# 05_PWMdriver.net
KiCad netlist of a schematic drawn in Altium Designer
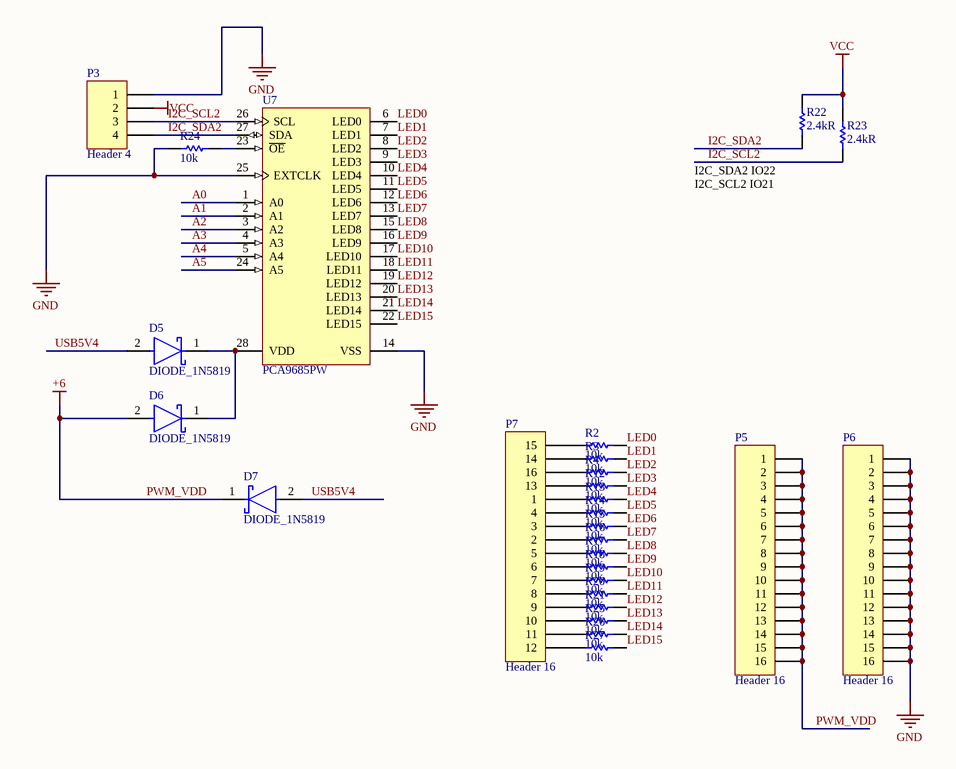
[diagram p0: 05_PWMdriver.SchDoc]

(export (version "E")
  (design (tool "Eeschema 10.0.6"))
  (components
    (comp (ref "D5")
      (value "DIODE_1N5819")
      (footprint "FP-SOD123-MFG")
      (description "DIODE SCHOTTKY 40V 1A SOD123")
      (fields
        (field (name "OCTOPART") "https://octopart.com/1n5819hw-7-f-diodes+inc.-323197")
        (field (name "MANUFACTURER") "Diodes Inc")
      )
      (libsource (lib "Altium Content Vault") (part "1d6ec82d83fb6aee721767c19dac4b9"))
    )
    (comp (ref "D6")
      (value "DIODE_1N5819")
      (footprint "FP-SOD123-MFG")
      (description "DIODE SCHOTTKY 40V 1A SOD123")
      (fields
        (field (name "OCTOPART") "https://octopart.com/1n5819hw-7-f-diodes+inc.-323197")
        (field (name "MANUFACTURER") "Diodes Inc")
      )
      (libsource (lib "Altium Content Vault") (part "1d6ec82d83fb6aee721767c19dac4b9"))
    )
    (comp (ref "D7")
      (value "DIODE_1N5819")
      (footprint "FP-SOD123-MFG")
      (description "DIODE SCHOTTKY 40V 1A SOD123")
      (fields
        (field (name "OCTOPART") "https://octopart.com/1n5819hw-7-f-diodes+inc.-323197")
        (field (name "MANUFACTURER") "Diodes Inc")
      )
      (libsource (lib "Altium Content Vault") (part "1d6ec82d83fb6aee721767c19dac4b9"))
    )
    (comp (ref "P3")
      (value "Header 4")
      (footprint "HDR1X4")
      (description "Header, 4-Pin")
      (fields (field (name "PUBLISHER") "Altium Limited"))
      (libsource (lib "Miscellaneous Connectors") (part "Header 4"))
    )
    (comp (ref "P5")
      (value "Header 16")
      (footprint "HDR1X16")
      (description "Header, 16-Pin")
      (fields (field (name "PUBLISHER") "Altium Limited"))
      (libsource (lib "Miscellaneous Connectors") (part "Header 16"))
    )
    (comp (ref "P6")
      (value "Header 16")
      (footprint "HDR1X16")
      (description "Header, 16-Pin")
      (fields (field (name "PUBLISHER") "Altium Limited"))
      (libsource (lib "Miscellaneous Connectors") (part "Header 16"))
    )
    (comp (ref "P7")
      (value "Header 16")
      (footprint "HDR1X16")
      (description "Header, 16-Pin")
      (fields (field (name "PUBLISHER") "Altium Limited"))
      (libsource (lib "") (part "Header 16_1"))
    )
    (comp (ref "R2")
      (value "10k")
      (footprint "RESC1609X55X30LL15T15")
      (description "Chip Resistor, 10 KOhm, +/- 1%, 0.1 W, -55 to 155 degC, 0603 (1608 Metric), RoHS, Tape and Reel")
      (fields (field (name "TOLERANCE") "1%") (field (name "MANUFACTURER") "Panasonic"))
      (libsource (lib "Altium Content Vault") (part "RES-2"))
    )
    (comp (ref "R3")
      (value "10k")
      (footprint "RESC1609X55X30LL15T15")
      (description "Chip Resistor, 10 KOhm, +/- 1%, 0.1 W, -55 to 155 degC, 0603 (1608 Metric), RoHS, Tape and Reel")
      (fields (field (name "TOLERANCE") "1%") (field (name "MANUFACTURER") "Panasonic"))
      (libsource (lib "Altium Content Vault") (part "RES-2"))
    )
    (comp (ref "R4")
      (value "10k")
      (footprint "RESC1609X55X30LL15T15")
      (description "Chip Resistor, 10 KOhm, +/- 1%, 0.1 W, -55 to 155 degC, 0603 (1608 Metric), RoHS, Tape and Reel")
      (fields (field (name "TOLERANCE") "1%") (field (name "MANUFACTURER") "Panasonic"))
      (libsource (lib "Altium Content Vault") (part "RES-2"))
    )
    (comp (ref "R12")
      (value "10k")
      (footprint "RESC1609X55X30LL15T15")
      (description "Chip Resistor, 10 KOhm, +/- 1%, 0.1 W, -55 to 155 degC, 0603 (1608 Metric), RoHS, Tape and Reel")
      (fields (field (name "TOLERANCE") "1%") (field (name "MANUFACTURER") "Panasonic"))
      (libsource (lib "Altium Content Vault") (part "RES-2"))
    )
    (comp (ref "R13")
      (value "10k")
      (footprint "RESC1609X55X30LL15T15")
      (description "Chip Resistor, 10 KOhm, +/- 1%, 0.1 W, -55 to 155 degC, 0603 (1608 Metric), RoHS, Tape and Reel")
      (fields (field (name "TOLERANCE") "1%") (field (name "MANUFACTURER") "Panasonic"))
      (libsource (lib "Altium Content Vault") (part "RES-2"))
    )
    (comp (ref "R14")
      (value "10k")
      (footprint "RESC1609X55X30LL15T15")
      (description "Chip Resistor, 10 KOhm, +/- 1%, 0.1 W, -55 to 155 degC, 0603 (1608 Metric), RoHS, Tape and Reel")
      (fields (field (name "TOLERANCE") "1%") (field (name "MANUFACTURER") "Panasonic"))
      (libsource (lib "Altium Content Vault") (part "RES-2"))
    )
    (comp (ref "R15")
      (value "10k")
      (footprint "RESC1609X55X30LL15T15")
      (description "Chip Resistor, 10 KOhm, +/- 1%, 0.1 W, -55 to 155 degC, 0603 (1608 Metric), RoHS, Tape and Reel")
      (fields (field (name "TOLERANCE") "1%") (field (name "MANUFACTURER") "Panasonic"))
      (libsource (lib "Altium Content Vault") (part "RES-2"))
    )
    (comp (ref "R16")
      (value "10k")
      (footprint "RESC1609X55X30LL15T15")
      (description "Chip Resistor, 10 KOhm, +/- 1%, 0.1 W, -55 to 155 degC, 0603 (1608 Metric), RoHS, Tape and Reel")
      (fields (field (name "TOLERANCE") "1%") (field (name "MANUFACTURER") "Panasonic"))
      (libsource (lib "Altium Content Vault") (part "RES-2"))
    )
    (comp (ref "R17")
      (value "10k")
      (footprint "RESC1609X55X30LL15T15")
      (description "Chip Resistor, 10 KOhm, +/- 1%, 0.1 W, -55 to 155 degC, 0603 (1608 Metric), RoHS, Tape and Reel")
      (fields (field (name "TOLERANCE") "1%") (field (name "MANUFACTURER") "Panasonic"))
      (libsource (lib "Altium Content Vault") (part "RES-2"))
    )
    (comp (ref "R18")
      (value "10k")
      (footprint "RESC1609X55X30LL15T15")
      (description "Chip Resistor, 10 KOhm, +/- 1%, 0.1 W, -55 to 155 degC, 0603 (1608 Metric), RoHS, Tape and Reel")
      (fields (field (name "TOLERANCE") "1%") (field (name "MANUFACTURER") "Panasonic"))
      (libsource (lib "Altium Content Vault") (part "RES-2"))
    )
    (comp (ref "R19")
      (value "10k")
      (footprint "RESC1609X55X30LL15T15")
      (description "Chip Resistor, 10 KOhm, +/- 1%, 0.1 W, -55 to 155 degC, 0603 (1608 Metric), RoHS, Tape and Reel")
      (fields (field (name "TOLERANCE") "1%") (field (name "MANUFACTURER") "Panasonic"))
      (libsource (lib "Altium Content Vault") (part "RES-2"))
    )
    (comp (ref "R20")
      (value "10k")
      (footprint "RESC1609X55X30LL15T15")
      (description "Chip Resistor, 10 KOhm, +/- 1%, 0.1 W, -55 to 155 degC, 0603 (1608 Metric), RoHS, Tape and Reel")
      (fields (field (name "TOLERANCE") "1%") (field (name "MANUFACTURER") "Panasonic"))
      (libsource (lib "Altium Content Vault") (part "RES-2"))
    )
    (comp (ref "R21")
      (value "10k")
      (footprint "RESC1609X55X30LL15T15")
      (description "Chip Resistor, 10 KOhm, +/- 1%, 0.1 W, -55 to 155 degC, 0603 (1608 Metric), RoHS, Tape and Reel")
      (fields (field (name "TOLERANCE") "1%") (field (name "MANUFACTURER") "Panasonic"))
      (libsource (lib "Altium Content Vault") (part "RES-2"))
    )
    (comp (ref "R22")
      (value "2.4kR")
      (footprint "RESC1608X50X30ML20T20")
      (fields
        (field (name "PART NUMBER") "RR0816P-242-D")
        (field (name "MANUFACTURER") "Susumu")
        (field (name "Comment") "R0603_2.4K")
      )
      (libsource (lib "Altium Content Vault") (part "RES"))
    )
    (comp (ref "R23")
      (value "2.4kR")
      (footprint "RESC1608X50X30ML20T20")
      (fields
        (field (name "PART NUMBER") "RR0816P-242-D")
        (field (name "MANUFACTURER") "Susumu")
        (field (name "Comment") "R0603_2.4K")
      )
      (libsource (lib "Altium Content Vault") (part "RES"))
    )
    (comp (ref "R24")
      (value "10k")
      (footprint "RESC1609X55X30LL15T15")
      (description "Chip Resistor, 10 KOhm, +/- 1%, 0.1 W, -55 to 155 degC, 0603 (1608 Metric), RoHS, Tape and Reel")
      (fields (field (name "TOLERANCE") "1%") (field (name "MANUFACTURER") "Panasonic"))
      (libsource (lib "Altium Content Vault") (part "RES-2"))
    )
    (comp (ref "R25")
      (value "10k")
      (footprint "RESC1609X55X30LL15T15")
      (description "Chip Resistor, 10 KOhm, +/- 1%, 0.1 W, -55 to 155 degC, 0603 (1608 Metric), RoHS, Tape and Reel")
      (fields (field (name "TOLERANCE") "1%") (field (name "MANUFACTURER") "Panasonic"))
      (libsource (lib "Altium Content Vault") (part "RES-2"))
    )
    (comp (ref "R26")
      (value "10k")
      (footprint "RESC1609X55X30LL15T15")
      (description "Chip Resistor, 10 KOhm, +/- 1%, 0.1 W, -55 to 155 degC, 0603 (1608 Metric), RoHS, Tape and Reel")
      (fields (field (name "TOLERANCE") "1%") (field (name "MANUFACTURER") "Panasonic"))
      (libsource (lib "Altium Content Vault") (part "RES-2"))
    )
    (comp (ref "R27")
      (value "10k")
      (footprint "RESC1609X55X30LL15T15")
      (description "Chip Resistor, 10 KOhm, +/- 1%, 0.1 W, -55 to 155 degC, 0603 (1608 Metric), RoHS, Tape and Reel")
      (fields (field (name "TOLERANCE") "1%") (field (name "MANUFACTURER") "Panasonic"))
      (libsource (lib "Altium Content Vault") (part "RES-2"))
    )
    (comp (ref "U7")
      (value "PCA9685PW")
      (footprint "SOT361-1_V")
      (fields (field (name "PARTNUMBER") "PCA9685"))
      (libsource (lib "Altium Content Vault") (part "NXP-PCA9685-SOT361-1"))
    )
  )
  (nets
    (net (code "1") (name "+6") (class "Default")
      (node (ref "D6") (pin "2") (pinfunction "A_2") (pintype "passive"))
      (node (ref "D7") (pin "1") (pinfunction "C_1") (pintype "passive"))
      (node (ref "P5") (pin "1") (pinfunction "1_1") (pintype "passive"))
      (node (ref "P5") (pin "10") (pinfunction "10_10") (pintype "passive"))
      (node (ref "P5") (pin "11") (pinfunction "11_11") (pintype "passive"))
      (node (ref "P5") (pin "12") (pinfunction "12_12") (pintype "passive"))
      (node (ref "P5") (pin "13") (pinfunction "13_13") (pintype "passive"))
      (node (ref "P5") (pin "14") (pinfunction "14_14") (pintype "passive"))
      (node (ref "P5") (pin "15") (pinfunction "15_15") (pintype "passive"))
      (node (ref "P5") (pin "16") (pinfunction "16_16") (pintype "passive"))
      (node (ref "P5") (pin "2") (pinfunction "2_2") (pintype "passive"))
      (node (ref "P5") (pin "3") (pinfunction "3_3") (pintype "passive"))
      (node (ref "P5") (pin "4") (pinfunction "4_4") (pintype "passive"))
      (node (ref "P5") (pin "5") (pinfunction "5_5") (pintype "passive"))
      (node (ref "P5") (pin "6") (pinfunction "6_6") (pintype "passive"))
      (node (ref "P5") (pin "7") (pinfunction "7_7") (pintype "passive"))
      (node (ref "P5") (pin "8") (pinfunction "8_8") (pintype "passive"))
      (node (ref "P5") (pin "9") (pinfunction "9_9") (pintype "passive"))
    )
    (net (code "2") (name "/A0") (class "Default")
      (node (ref "U7") (pin "1") (pinfunction "A0_1") (pintype "input"))
    )
    (net (code "3") (name "/A1") (class "Default")
      (node (ref "U7") (pin "2") (pinfunction "A1_2") (pintype "input"))
    )
    (net (code "4") (name "/A2") (class "Default")
      (node (ref "U7") (pin "3") (pinfunction "A2_3") (pintype "input"))
    )
    (net (code "5") (name "/A3") (class "Default")
      (node (ref "U7") (pin "4") (pinfunction "A3_4") (pintype "input"))
    )
    (net (code "6") (name "/A4") (class "Default")
      (node (ref "U7") (pin "5") (pinfunction "A4_5") (pintype "input"))
    )
    (net (code "7") (name "/A5") (class "Default")
      (node (ref "U7") (pin "24") (pinfunction "A5_24") (pintype "input"))
    )
    (net (code "8") (name "/I2C_SCL2") (class "Default")
      (node (ref "P3") (pin "3") (pinfunction "3_3") (pintype "passive"))
      (node (ref "R23") (pin "1") (pinfunction "1_1") (pintype "passive"))
      (node (ref "U7") (pin "26") (pinfunction "SCL_26") (pintype "input"))
    )
    (net (code "9") (name "/I2C_SDA2") (class "Default")
      (node (ref "P3") (pin "4") (pinfunction "4_4") (pintype "passive"))
      (node (ref "R22") (pin "1") (pinfunction "1_1") (pintype "passive"))
      (node (ref "U7") (pin "27") (pinfunction "SDA_27") (pintype "bidirectional"))
    )
    (net (code "10") (name "/LED0") (class "Default")
      (node (ref "R2") (pin "1") (pinfunction "1_1") (pintype "passive"))
      (node (ref "U7") (pin "6") (pinfunction "LED0_6") (pintype "tri_state"))
    )
    (net (code "11") (name "/LED1") (class "Default")
      (node (ref "R3") (pin "1") (pinfunction "1_1") (pintype "passive"))
      (node (ref "U7") (pin "7") (pinfunction "LED1_7") (pintype "tri_state"))
    )
    (net (code "12") (name "/LED2") (class "Default")
      (node (ref "R4") (pin "1") (pinfunction "1_1") (pintype "passive"))
      (node (ref "U7") (pin "8") (pinfunction "LED2_8") (pintype "tri_state"))
    )
    (net (code "13") (name "/LED3") (class "Default")
      (node (ref "R12") (pin "1") (pinfunction "1_1") (pintype "passive"))
      (node (ref "U7") (pin "9") (pinfunction "LED3_9") (pintype "tri_state"))
    )
    (net (code "14") (name "/LED4") (class "Default")
      (node (ref "R13") (pin "1") (pinfunction "1_1") (pintype "passive"))
      (node (ref "U7") (pin "10") (pinfunction "LED4_10") (pintype "tri_state"))
    )
    (net (code "15") (name "/LED5") (class "Default")
      (node (ref "R14") (pin "1") (pinfunction "1_1") (pintype "passive"))
      (node (ref "U7") (pin "11") (pinfunction "LED5_11") (pintype "tri_state"))
    )
    (net (code "16") (name "/LED6") (class "Default")
      (node (ref "R15") (pin "1") (pinfunction "1_1") (pintype "passive"))
      (node (ref "U7") (pin "12") (pinfunction "LED6_12") (pintype "tri_state"))
    )
    (net (code "17") (name "/LED7") (class "Default")
      (node (ref "R16") (pin "1") (pinfunction "1_1") (pintype "passive"))
      (node (ref "U7") (pin "13") (pinfunction "LED7_13") (pintype "tri_state"))
    )
    (net (code "18") (name "/LED8") (class "Default")
      (node (ref "R17") (pin "1") (pinfunction "1_1") (pintype "passive"))
      (node (ref "U7") (pin "15") (pinfunction "LED8_15") (pintype "tri_state"))
    )
    (net (code "19") (name "/LED9") (class "Default")
      (node (ref "R18") (pin "1") (pinfunction "1_1") (pintype "passive"))
      (node (ref "U7") (pin "16") (pinfunction "LED9_16") (pintype "tri_state"))
    )
    (net (code "20") (name "/LED10") (class "Default")
      (node (ref "R19") (pin "1") (pinfunction "1_1") (pintype "passive"))
      (node (ref "U7") (pin "17") (pinfunction "LED10_17") (pintype "tri_state"))
    )
    (net (code "21") (name "/LED11") (class "Default")
      (node (ref "R20") (pin "1") (pinfunction "1_1") (pintype "passive"))
      (node (ref "U7") (pin "18") (pinfunction "LED11_18") (pintype "tri_state"))
    )
    (net (code "22") (name "/LED12") (class "Default")
      (node (ref "R21") (pin "1") (pinfunction "1_1") (pintype "passive"))
      (node (ref "U7") (pin "19") (pinfunction "LED12_19") (pintype "tri_state"))
    )
    (net (code "23") (name "/LED13") (class "Default")
      (node (ref "R25") (pin "1") (pinfunction "1_1") (pintype "passive"))
      (node (ref "U7") (pin "20") (pinfunction "LED13_20") (pintype "tri_state"))
    )
    (net (code "24") (name "/LED14") (class "Default")
      (node (ref "R26") (pin "1") (pinfunction "1_1") (pintype "passive"))
      (node (ref "U7") (pin "21") (pinfunction "LED14_21") (pintype "tri_state"))
    )
    (net (code "25") (name "/LED15") (class "Default")
      (node (ref "R27") (pin "1") (pinfunction "1_1") (pintype "passive"))
      (node (ref "U7") (pin "22") (pinfunction "LED15_22") (pintype "tri_state"))
    )
    (net (code "26") (name "/USB5V4") (class "Default")
      (node (ref "D5") (pin "2") (pinfunction "A_2") (pintype "passive"))
      (node (ref "D7") (pin "2") (pinfunction "A_2") (pintype "passive"))
    )
    (net (code "27") (name "GND") (class "Default")
      (node (ref "P3") (pin "1") (pinfunction "1_1") (pintype "passive"))
      (node (ref "P6") (pin "1") (pinfunction "1_1") (pintype "passive"))
      (node (ref "P6") (pin "10") (pinfunction "10_10") (pintype "passive"))
      (node (ref "P6") (pin "11") (pinfunction "11_11") (pintype "passive"))
      (node (ref "P6") (pin "12") (pinfunction "12_12") (pintype "passive"))
      (node (ref "P6") (pin "13") (pinfunction "13_13") (pintype "passive"))
      (node (ref "P6") (pin "14") (pinfunction "14_14") (pintype "passive"))
      (node (ref "P6") (pin "15") (pinfunction "15_15") (pintype "passive"))
      (node (ref "P6") (pin "16") (pinfunction "16_16") (pintype "passive"))
      (node (ref "P6") (pin "2") (pinfunction "2_2") (pintype "passive"))
      (node (ref "P6") (pin "3") (pinfunction "3_3") (pintype "passive"))
      (node (ref "P6") (pin "4") (pinfunction "4_4") (pintype "passive"))
      (node (ref "P6") (pin "5") (pinfunction "5_5") (pintype "passive"))
      (node (ref "P6") (pin "6") (pinfunction "6_6") (pintype "passive"))
      (node (ref "P6") (pin "7") (pinfunction "7_7") (pintype "passive"))
      (node (ref "P6") (pin "8") (pinfunction "8_8") (pintype "passive"))
      (node (ref "P6") (pin "9") (pinfunction "9_9") (pintype "passive"))
      (node (ref "R24") (pin "2") (pinfunction "2_2") (pintype "passive"))
      (node (ref "U7") (pin "14") (pinfunction "VSS_14") (pintype "power_in"))
      (node (ref "U7") (pin "25") (pinfunction "EXTCLK_25") (pintype "input"))
    )
    (net (code "28") (name "Net-(D5-C)") (class "Default")
      (node (ref "D5") (pin "1") (pinfunction "C_1") (pintype "passive"))
      (node (ref "D6") (pin "1") (pinfunction "C_1") (pintype "passive"))
      (node (ref "U7") (pin "28") (pinfunction "VDD_28") (pintype "power_in"))
    )
    (net (code "29") (name "Net-(P7-Pad1)") (class "Default")
      (node (ref "P7") (pin "1") (pinfunction "1_1") (pintype "passive"))
      (node (ref "R13") (pin "2") (pinfunction "2_2") (pintype "passive"))
    )
    (net (code "30") (name "Net-(P7-Pad2)") (class "Default")
      (node (ref "P7") (pin "2") (pinfunction "2_2") (pintype "passive"))
      (node (ref "R16") (pin "2") (pinfunction "2_2") (pintype "passive"))
    )
    (net (code "31") (name "Net-(P7-Pad3)") (class "Default")
      (node (ref "P7") (pin "3") (pinfunction "3_3") (pintype "passive"))
      (node (ref "R15") (pin "2") (pinfunction "2_2") (pintype "passive"))
    )
    (net (code "32") (name "Net-(P7-Pad4)") (class "Default")
      (node (ref "P7") (pin "4") (pinfunction "4_4") (pintype "passive"))
      (node (ref "R14") (pin "2") (pinfunction "2_2") (pintype "passive"))
    )
    (net (code "33") (name "Net-(P7-Pad5)") (class "Default")
      (node (ref "P7") (pin "5") (pinfunction "5_5") (pintype "passive"))
      (node (ref "R17") (pin "2") (pinfunction "2_2") (pintype "passive"))
    )
    (net (code "34") (name "Net-(P7-Pad6)") (class "Default")
      (node (ref "P7") (pin "6") (pinfunction "6_6") (pintype "passive"))
      (node (ref "R18") (pin "2") (pinfunction "2_2") (pintype "passive"))
    )
    (net (code "35") (name "Net-(P7-Pad7)") (class "Default")
      (node (ref "P7") (pin "7") (pinfunction "7_7") (pintype "passive"))
      (node (ref "R19") (pin "2") (pinfunction "2_2") (pintype "passive"))
    )
    (net (code "36") (name "Net-(P7-Pad8)") (class "Default")
      (node (ref "P7") (pin "8") (pinfunction "8_8") (pintype "passive"))
      (node (ref "R20") (pin "2") (pinfunction "2_2") (pintype "passive"))
    )
    (net (code "37") (name "Net-(P7-Pad9)") (class "Default")
      (node (ref "P7") (pin "9") (pinfunction "9_9") (pintype "passive"))
      (node (ref "R21") (pin "2") (pinfunction "2_2") (pintype "passive"))
    )
    (net (code "38") (name "Net-(P7-Pad10)") (class "Default")
      (node (ref "P7") (pin "10") (pinfunction "10_10") (pintype "passive"))
      (node (ref "R25") (pin "2") (pinfunction "2_2") (pintype "passive"))
    )
    (net (code "39") (name "Net-(P7-Pad11)") (class "Default")
      (node (ref "P7") (pin "11") (pinfunction "11_11") (pintype "passive"))
      (node (ref "R26") (pin "2") (pinfunction "2_2") (pintype "passive"))
    )
    (net (code "40") (name "Net-(P7-Pad12)") (class "Default")
      (node (ref "P7") (pin "12") (pinfunction "12_12") (pintype "passive"))
      (node (ref "R27") (pin "2") (pinfunction "2_2") (pintype "passive"))
    )
    (net (code "41") (name "Net-(P7-Pad13)") (class "Default")
      (node (ref "P7") (pin "13") (pinfunction "13_13") (pintype "passive"))
      (node (ref "R12") (pin "2") (pinfunction "2_2") (pintype "passive"))
    )
    (net (code "42") (name "Net-(P7-Pad14)") (class "Default")
      (node (ref "P7") (pin "14") (pinfunction "14_14") (pintype "passive"))
      (node (ref "R3") (pin "2") (pinfunction "2_2") (pintype "passive"))
    )
    (net (code "43") (name "Net-(P7-Pad15)") (class "Default")
      (node (ref "P7") (pin "15") (pinfunction "15_15") (pintype "passive"))
      (node (ref "R2") (pin "2") (pinfunction "2_2") (pintype "passive"))
    )
    (net (code "44") (name "Net-(P7-Pad16)") (class "Default")
      (node (ref "P7") (pin "16") (pinfunction "16_16") (pintype "passive"))
      (node (ref "R4") (pin "2") (pinfunction "2_2") (pintype "passive"))
    )
    (net (code "45") (name "Net-(U7-~{OE})") (class "Default")
      (node (ref "R24") (pin "1") (pinfunction "1_1") (pintype "passive"))
      (node (ref "U7") (pin "23") (pinfunction "~{OE}_23") (pintype "input"))
    )
    (net (code "46") (name "VCC") (class "Default")
      (node (ref "P3") (pin "2") (pinfunction "2_2") (pintype "passive"))
      (node (ref "R22") (pin "2") (pinfunction "2_2") (pintype "passive"))
      (node (ref "R23") (pin "2") (pinfunction "2_2") (pintype "passive"))
    )
  )
)
